# Arduino_UNO_Zeno_Version_2021-05-13.net
KiCad netlist of a schematic drawn in EasyEDA
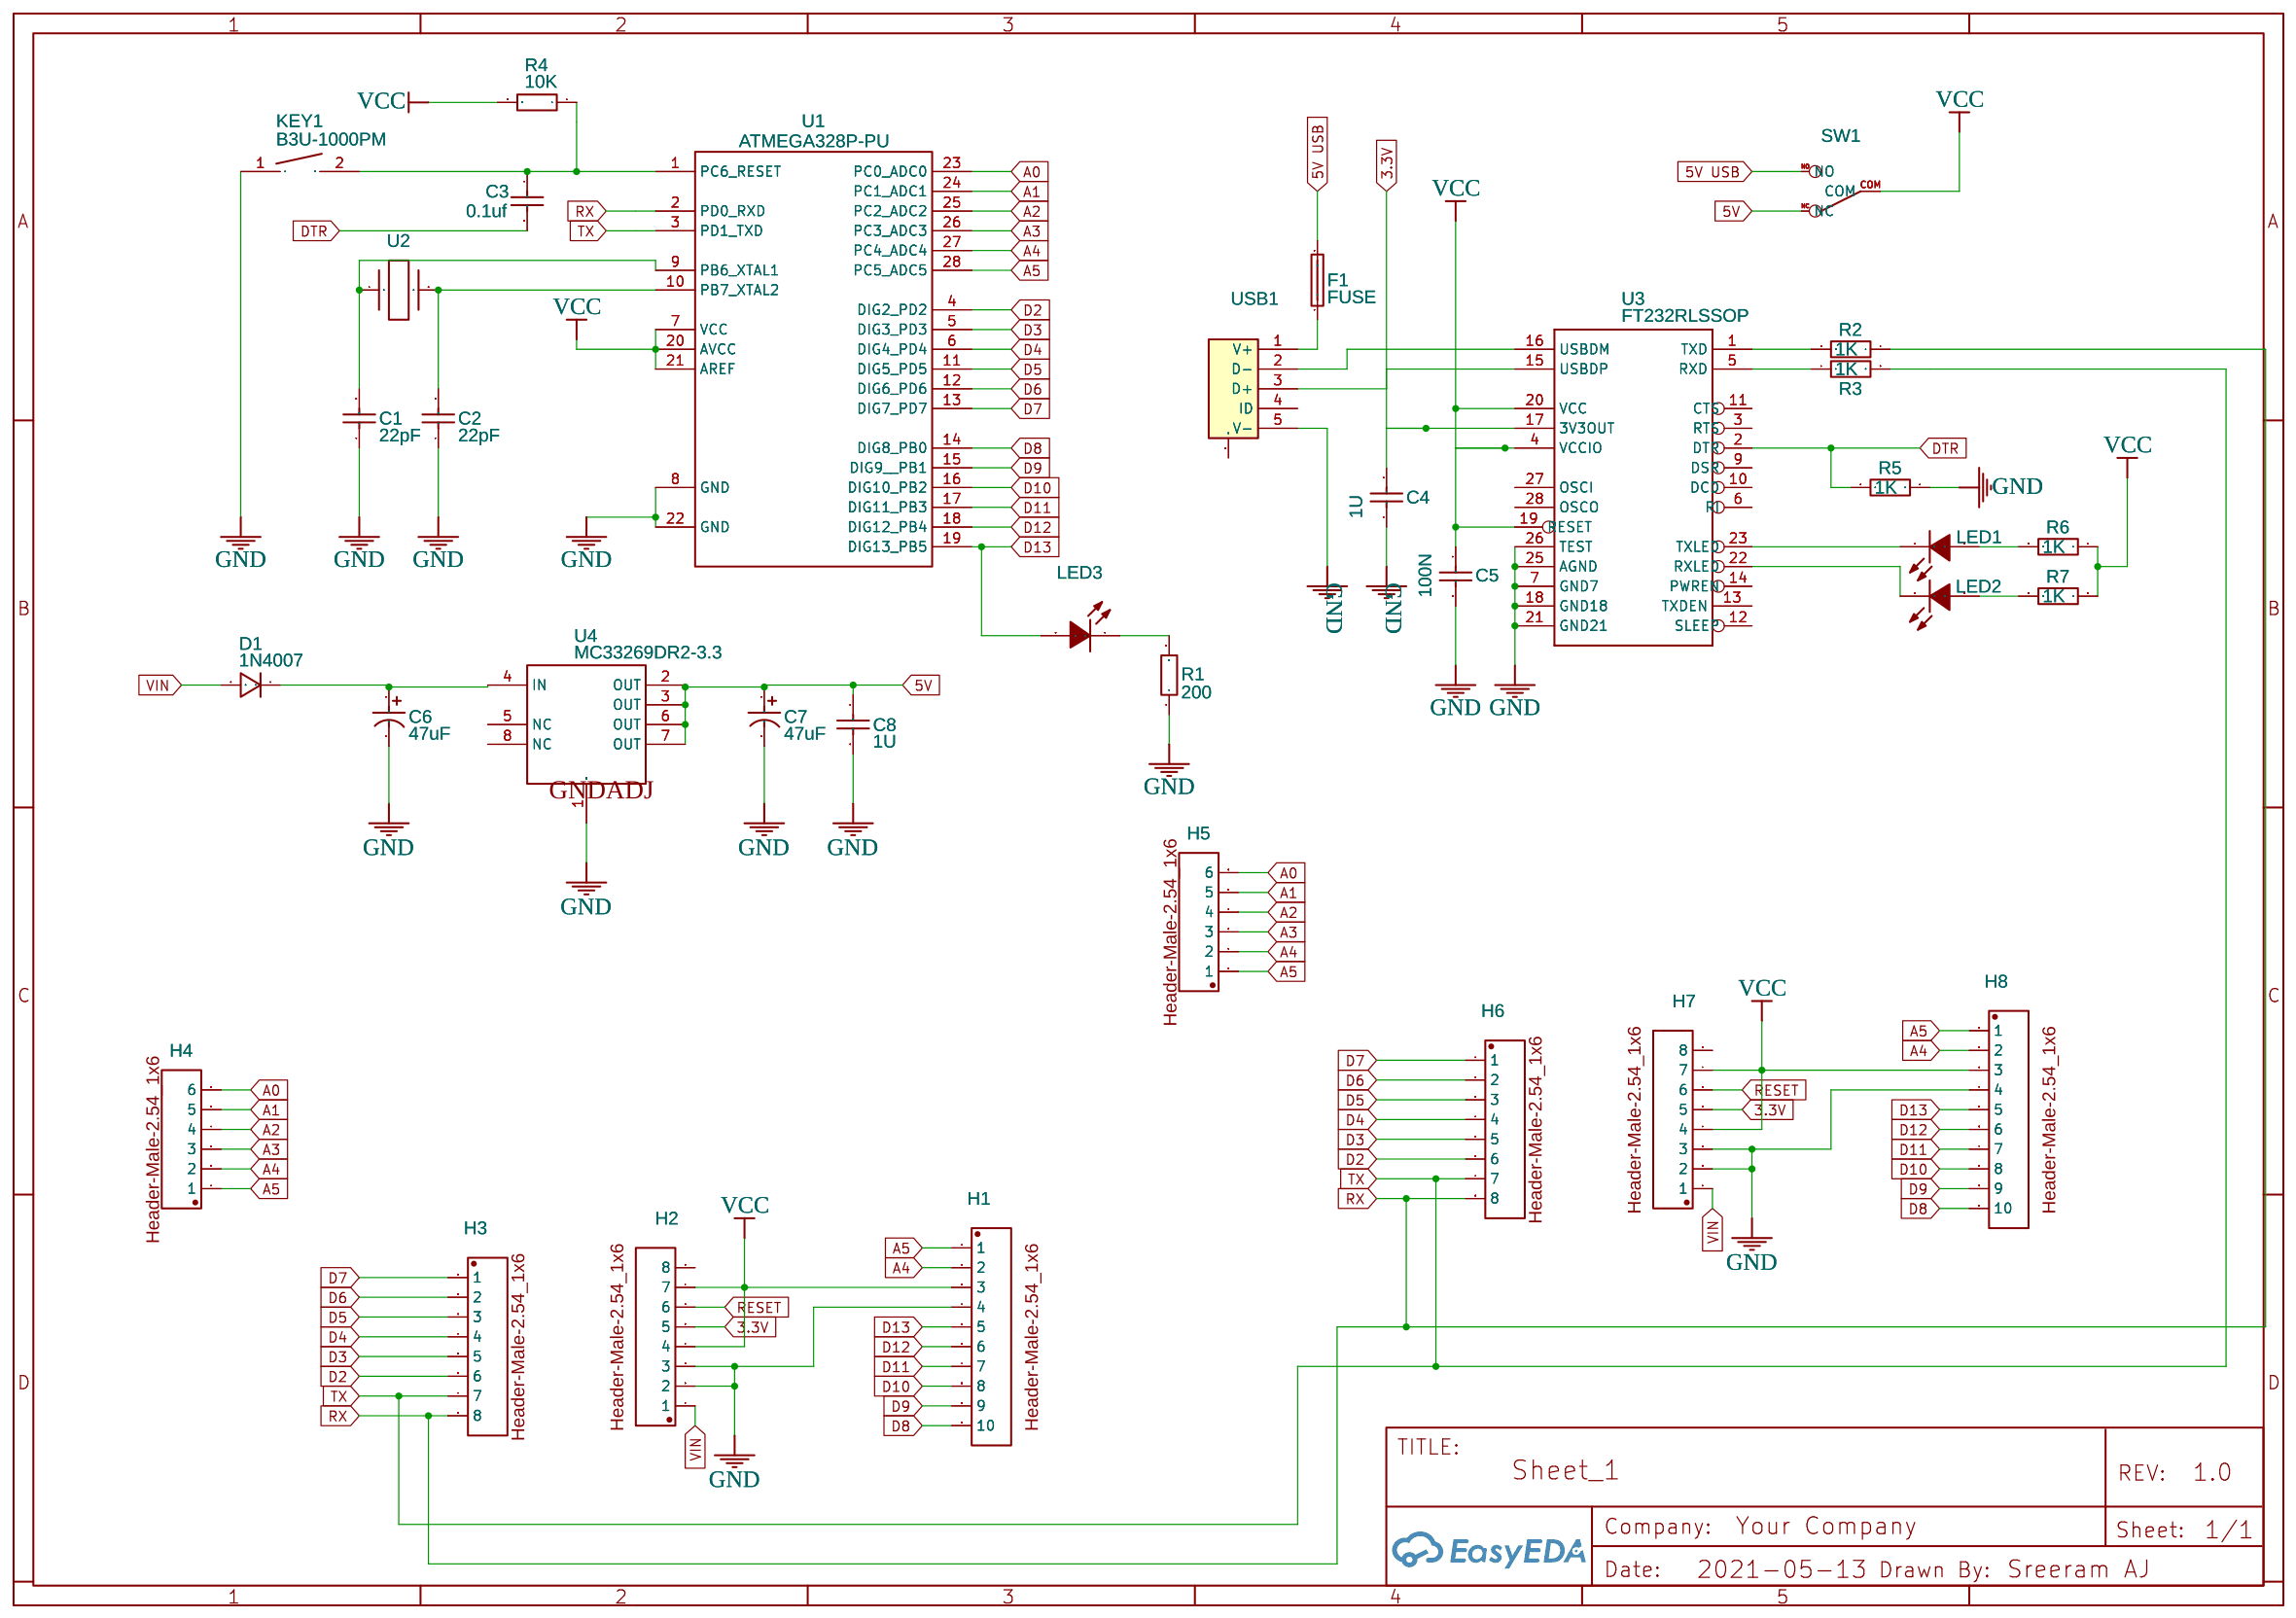
[diagram p0: schematic sheet]

(export (version "E")
  (design (tool "Eeschema 10.0.6"))
  (components
    (comp (ref "C1")
      (value "22pF")
      (fields
        (field (name "BOM_Manufacturer Part") "1206CG220J500NT")
        (field (name "BOM_Supplier Part") "C1896")
      )
      (libsource (lib "") (part "CAPACITOR SMD  22pF 1206"))
    )
    (comp (ref "C2")
      (value "22pF")
      (fields
        (field (name "BOM_Manufacturer Part") "1206CG220J500NT")
        (field (name "BOM_Supplier Part") "C1896")
      )
      (libsource (lib "") (part "CAPACITOR SMD  22pF 1206"))
    )
    (comp (ref "C3")
      (value "0.1uf")
      (fields
        (field (name "BOM_Manufacturer Part") "1206CG220J500NT")
        (field (name "BOM_Supplier Part") "C1896")
      )
      (libsource (lib "") (part "CAPACITOR SMD  22pF 1206_1"))
    )
    (comp (ref "C4")
      (value "1U")
      (fields
        (field (name "BOM_Manufacturer Part") "1206CG220J500NT")
        (field (name "BOM_Supplier Part") "C1896")
      )
      (libsource (lib "") (part "CAPACITOR SMD  22pF 1206"))
    )
    (comp (ref "C5")
      (value "100N")
      (fields
        (field (name "BOM_Manufacturer Part") "1206CG220J500NT")
        (field (name "BOM_Supplier Part") "C1896")
      )
      (libsource (lib "") (part "CAPACITOR SMD  22pF 1206_1"))
    )
    (comp (ref "C6")
      (value "47uF")
      (fields
        (field (name "BOM_Manufacturer Part") "EEE-1JA470UP")
        (field (name "BOM_Supplier Part") "PCE3946CT-ND")
      )
      (libsource (lib "") (part "PCE3946CT-ND 47UF 63V SMD CAPACITOR"))
    )
    (comp (ref "C7")
      (value "47uF")
      (fields
        (field (name "BOM_Manufacturer Part") "EEE-1JA470UP")
        (field (name "BOM_Supplier Part") "PCE3946CT-ND")
      )
      (libsource (lib "") (part "PCE3946CT-ND 47UF 63V SMD CAPACITOR"))
    )
    (comp (ref "C8")
      (value "1U")
      (fields
        (field (name "BOM_Manufacturer Part") "1206CG220J500NT")
        (field (name "BOM_Supplier Part") "C1896")
      )
      (libsource (lib "") (part "CAPACITOR SMD  22pF 1206_1"))
    )
    (comp (ref "D1")
      (value "1N4007")
      (fields (field (name "BOM_Supplier Part") "C126233"))
      (libsource (lib "") (part "DIODE 1N4007 SMD 5X2.56"))
    )
    (comp (ref "F1")
      (value "FUSE")
      (fields
        (field (name "BOM_Manufacturer Part") "1812L020PR")
        (field (name "BOM_Supplier Part") "C151167")
      )
      (libsource (lib "") (part "1812L020PR"))
    )
    (comp (ref "H1") (value "Header-Male-2.54_1x10") (libsource (lib "") (part "Header-Male-2.54_1x10")))
    (comp (ref "H2") (value "HEADER-MALE-2.54_1X8") (libsource (lib "") (part "HEADER-MALE-2.54_1X8_1")))
    (comp (ref "H3") (value "K") (libsource (lib "") (part "HEADER-MALE-2.54_1X8")))
    (comp (ref "H4") (value "Header-Male-2.54_1x6") (libsource (lib "") (part "Header-Male-2.54_1x6")))
    (comp (ref "H5") (value "Header-Male-2.54_1x6") (libsource (lib "") (part "Header-Male-2.54_1x6")))
    (comp (ref "H6") (value "K") (libsource (lib "") (part "HEADER-MALE-2.54_1X8")))
    (comp (ref "H7") (value "HEADER-MALE-2.54_1X8") (libsource (lib "") (part "HEADER-MALE-2.54_1X8_1")))
    (comp (ref "H8") (value "Header-Male-2.54_1x10") (libsource (lib "") (part "Header-Male-2.54_1x10")))
    (comp (ref "KEY1")
      (value "B3U-1000PM")
      (fields (field (name "BOM_Supplier Part") "C271754"))
      (libsource (lib "") (part "B3U-1000PM"))
    )
    (comp (ref "LED1") (value "LED SMD 0603") (libsource (lib "") (part "LED SMD 0603")))
    (comp (ref "LED2") (value "LED SMD 0603") (libsource (lib "") (part "LED SMD 0603")))
    (comp (ref "LED3") (value "LED SMD 0603") (libsource (lib "") (part "LED SMD 0603_1")))
    (comp (ref "R1")
      (value "200")
      (fields
        (field (name "BOM_Manufacturer Part") "RS-03K102JT")
        (field (name "BOM_Supplier Part") "C73797")
      )
      (libsource (lib "") (part "1k Resistor SMD 0603 (C73797)_2"))
    )
    (comp (ref "R2")
      (value "1K")
      (fields
        (field (name "BOM_Manufacturer Part") "RS-03K102JT")
        (field (name "BOM_Supplier Part") "C73797")
      )
      (libsource (lib "") (part "1k Resistor SMD 0603 (C73797)_1"))
    )
    (comp (ref "R3")
      (value "1K")
      (fields
        (field (name "BOM_Manufacturer Part") "RS-03K102JT")
        (field (name "BOM_Supplier Part") "C73797")
      )
      (libsource (lib "") (part "1k Resistor SMD 0603 (C73797)"))
    )
    (comp (ref "R4")
      (value "10K")
      (fields
        (field (name "BOM_Manufacturer Part") "RS-03K102JT")
        (field (name "BOM_Supplier Part") "C73797")
      )
      (libsource (lib "") (part "1k Resistor SMD 0603 (C73797)_1"))
    )
    (comp (ref "R5")
      (value "1K")
      (fields
        (field (name "BOM_Manufacturer Part") "RS-03K102JT")
        (field (name "BOM_Supplier Part") "C73797")
      )
      (libsource (lib "") (part "1k Resistor SMD 0603 (C73797)_1"))
    )
    (comp (ref "R6")
      (value "1K")
      (fields
        (field (name "BOM_Manufacturer Part") "RS-03K102JT")
        (field (name "BOM_Supplier Part") "C73797")
      )
      (libsource (lib "") (part "1k Resistor SMD 0603 (C73797)_1"))
    )
    (comp (ref "R7")
      (value "1K")
      (fields
        (field (name "BOM_Manufacturer Part") "RS-03K102JT")
        (field (name "BOM_Supplier Part") "C73797")
      )
      (libsource (lib "") (part "1k Resistor SMD 0603 (C73797)_1"))
    )
    (comp (ref "SW1") (value "SW_SLIDE") (libsource (lib "") (part "SW_SLIDE")))
    (comp (ref "U1")
      (value "ATMEGA328P-PU")
      (fields (field (name "BOM_Supplier Part") "C33901"))
      (libsource (lib "") (part "ATMEGA328P-PU"))
    )
    (comp (ref "U2")
      (value "Crystal resonator 12 MHz")
      (libsource (lib "") (part "Crystal resonator 12 MHz"))
    )
    (comp (ref "U3") (value "FT232RLSSOP") (libsource (lib "") (part "FT232RLSSOP")))
    (comp (ref "U4")
      (value "MC33269DR2-3.3")
      (fields (field (name "BOM_Supplier Part") "C7301"))
      (libsource (lib "") (part "MC33269DR2-3.3"))
    )
    (comp (ref "USB1")
      (value "micro USBFemale")
      (fields (field (name "BOM_Supplier Part") "C10418"))
      (libsource (lib "") (part "micro USBFemale"))
    )
  )
  (nets
    (net (code "1") (name "3.3V") (class "Default")
      (node (ref "C4") (pin "2") (pinfunction "2_2") (pintype "input"))
      (node (ref "H2") (pin "5") (pinfunction "5_5") (pintype "unspecified"))
      (node (ref "H7") (pin "5") (pinfunction "5_5") (pintype "unspecified"))
      (node (ref "U3") (pin "17") (pinfunction "3V3OUT_17") (pintype "output"))
    )
    (net (code "2") (name "5V") (class "Default")
      (node (ref "C7") (pin "1") (pinfunction "1_1") (pintype "input"))
      (node (ref "C8") (pin "1") (pinfunction "1_1") (pintype "input"))
      (node (ref "SW1") (pin "NC") (pinfunction "NC_NC") (pintype "unspecified"))
      (node (ref "U4") (pin "2") (pinfunction "OUT_2") (pintype "passive"))
      (node (ref "U4") (pin "3") (pinfunction "OUT_3") (pintype "passive"))
      (node (ref "U4") (pin "6") (pinfunction "OUT_6") (pintype "passive"))
      (node (ref "U4") (pin "7") (pinfunction "OUT_7") (pintype "passive"))
    )
    (net (code "3") (name "5V USB") (class "Default")
      (node (ref "F1") (pin "2") (pinfunction "2_2") (pintype "unspecified"))
      (node (ref "SW1") (pin "NO") (pinfunction "NO_NO") (pintype "unspecified"))
    )
    (net (code "4") (name "A0") (class "Default")
      (node (ref "H4") (pin "6") (pinfunction "6_6") (pintype "unspecified"))
      (node (ref "H5") (pin "6") (pinfunction "6_6") (pintype "unspecified"))
      (node (ref "U1") (pin "23") (pinfunction "PC0_ADC0_23") (pintype "bidirectional"))
    )
    (net (code "5") (name "A1") (class "Default")
      (node (ref "H4") (pin "5") (pinfunction "5_5") (pintype "unspecified"))
      (node (ref "H5") (pin "5") (pinfunction "5_5") (pintype "unspecified"))
      (node (ref "U1") (pin "24") (pinfunction "PC1_ADC1_24") (pintype "bidirectional"))
    )
    (net (code "6") (name "A2") (class "Default")
      (node (ref "H4") (pin "4") (pinfunction "4_4") (pintype "unspecified"))
      (node (ref "H5") (pin "4") (pinfunction "4_4") (pintype "unspecified"))
      (node (ref "U1") (pin "25") (pinfunction "PC2_ADC2_25") (pintype "bidirectional"))
    )
    (net (code "7") (name "A3") (class "Default")
      (node (ref "H4") (pin "3") (pinfunction "3_3") (pintype "unspecified"))
      (node (ref "H5") (pin "3") (pinfunction "3_3") (pintype "unspecified"))
      (node (ref "U1") (pin "26") (pinfunction "PC3_ADC3_26") (pintype "bidirectional"))
    )
    (net (code "8") (name "A4") (class "Default")
      (node (ref "H1") (pin "2") (pinfunction "2_2") (pintype "unspecified"))
      (node (ref "H4") (pin "2") (pinfunction "2_2") (pintype "unspecified"))
      (node (ref "H5") (pin "2") (pinfunction "2_2") (pintype "unspecified"))
      (node (ref "H8") (pin "2") (pinfunction "2_2") (pintype "unspecified"))
      (node (ref "U1") (pin "27") (pinfunction "PC4_ADC4_27") (pintype "bidirectional"))
    )
    (net (code "9") (name "A5") (class "Default")
      (node (ref "H1") (pin "1") (pinfunction "1_1") (pintype "unspecified"))
      (node (ref "H4") (pin "1") (pinfunction "1_1") (pintype "unspecified"))
      (node (ref "H5") (pin "1") (pinfunction "1_1") (pintype "unspecified"))
      (node (ref "H8") (pin "1") (pinfunction "1_1") (pintype "unspecified"))
      (node (ref "U1") (pin "28") (pinfunction "PC5_ADC5_28") (pintype "bidirectional"))
    )
    (net (code "10") (name "D2") (class "Default")
      (node (ref "H3") (pin "6") (pinfunction "6_6") (pintype "unspecified"))
      (node (ref "H6") (pin "6") (pinfunction "6_6") (pintype "unspecified"))
      (node (ref "U1") (pin "4") (pinfunction "DIG2_PD2_4") (pintype "bidirectional"))
    )
    (net (code "11") (name "D3") (class "Default")
      (node (ref "H3") (pin "5") (pinfunction "5_5") (pintype "unspecified"))
      (node (ref "H6") (pin "5") (pinfunction "5_5") (pintype "unspecified"))
      (node (ref "U1") (pin "5") (pinfunction "DIG3_PD3_5") (pintype "bidirectional"))
    )
    (net (code "12") (name "D4") (class "Default")
      (node (ref "H3") (pin "4") (pinfunction "4_4") (pintype "unspecified"))
      (node (ref "H6") (pin "4") (pinfunction "4_4") (pintype "unspecified"))
      (node (ref "U1") (pin "6") (pinfunction "DIG4_PD4_6") (pintype "bidirectional"))
    )
    (net (code "13") (name "D5") (class "Default")
      (node (ref "H3") (pin "3") (pinfunction "3_3") (pintype "unspecified"))
      (node (ref "H6") (pin "3") (pinfunction "3_3") (pintype "unspecified"))
      (node (ref "U1") (pin "11") (pinfunction "DIG5_PD5_11") (pintype "bidirectional"))
    )
    (net (code "14") (name "D6") (class "Default")
      (node (ref "H3") (pin "2") (pinfunction "2_2") (pintype "unspecified"))
      (node (ref "H6") (pin "2") (pinfunction "2_2") (pintype "unspecified"))
      (node (ref "U1") (pin "12") (pinfunction "DIG6_PD6_12") (pintype "bidirectional"))
    )
    (net (code "15") (name "D7") (class "Default")
      (node (ref "H3") (pin "1") (pinfunction "1_1") (pintype "unspecified"))
      (node (ref "H6") (pin "1") (pinfunction "1_1") (pintype "unspecified"))
      (node (ref "U1") (pin "13") (pinfunction "DIG7_PD7_13") (pintype "bidirectional"))
    )
    (net (code "16") (name "D8") (class "Default")
      (node (ref "H1") (pin "10") (pinfunction "10_10") (pintype "unspecified"))
      (node (ref "H8") (pin "10") (pinfunction "10_10") (pintype "unspecified"))
      (node (ref "U1") (pin "14") (pinfunction "DIG8_PB0_14") (pintype "bidirectional"))
    )
    (net (code "17") (name "D9") (class "Default")
      (node (ref "H1") (pin "9") (pinfunction "9_9") (pintype "unspecified"))
      (node (ref "H8") (pin "9") (pinfunction "9_9") (pintype "unspecified"))
      (node (ref "U1") (pin "15") (pinfunction "DIG9__PB1_15") (pintype "bidirectional"))
    )
    (net (code "18") (name "D10") (class "Default")
      (node (ref "H1") (pin "8") (pinfunction "8_8") (pintype "unspecified"))
      (node (ref "H8") (pin "8") (pinfunction "8_8") (pintype "unspecified"))
      (node (ref "U1") (pin "16") (pinfunction "DIG10_PB2_16") (pintype "bidirectional"))
    )
    (net (code "19") (name "D11") (class "Default")
      (node (ref "H1") (pin "7") (pinfunction "7_7") (pintype "unspecified"))
      (node (ref "H8") (pin "7") (pinfunction "7_7") (pintype "unspecified"))
      (node (ref "U1") (pin "17") (pinfunction "DIG11_PB3_17") (pintype "bidirectional"))
    )
    (net (code "20") (name "D12") (class "Default")
      (node (ref "H1") (pin "6") (pinfunction "6_6") (pintype "unspecified"))
      (node (ref "H8") (pin "6") (pinfunction "6_6") (pintype "unspecified"))
      (node (ref "U1") (pin "18") (pinfunction "DIG12_PB4_18") (pintype "bidirectional"))
    )
    (net (code "21") (name "D13") (class "Default")
      (node (ref "H1") (pin "5") (pinfunction "5_5") (pintype "unspecified"))
      (node (ref "H8") (pin "5") (pinfunction "5_5") (pintype "unspecified"))
      (node (ref "LED3") (pin "2") (pinfunction "A_2") (pintype "unspecified"))
      (node (ref "U1") (pin "19") (pinfunction "DIG13_PB5_19") (pintype "bidirectional"))
    )
    (net (code "22") (name "DTR") (class "Default")
      (node (ref "C3") (pin "2") (pinfunction "2_2") (pintype "input"))
      (node (ref "R5") (pin "2") (pinfunction "2_2") (pintype "input"))
      (node (ref "U3") (pin "2") (pinfunction "DTR_2") (pintype "output"))
    )
    (net (code "23") (name "GND") (class "Default")
      (node (ref "C1") (pin "1") (pinfunction "1_1") (pintype "input"))
      (node (ref "C2") (pin "1") (pinfunction "1_1") (pintype "input"))
      (node (ref "C4") (pin "1") (pinfunction "1_1") (pintype "input"))
      (node (ref "C5") (pin "2") (pinfunction "2_2") (pintype "input"))
      (node (ref "C6") (pin "2") (pinfunction "2_2") (pintype "input"))
      (node (ref "C7") (pin "2") (pinfunction "2_2") (pintype "input"))
      (node (ref "C8") (pin "2") (pinfunction "2_2") (pintype "input"))
      (node (ref "H1") (pin "4") (pinfunction "4_4") (pintype "unspecified"))
      (node (ref "H2") (pin "2") (pinfunction "2_2") (pintype "unspecified"))
      (node (ref "H2") (pin "3") (pinfunction "3_3") (pintype "unspecified"))
      (node (ref "H7") (pin "2") (pinfunction "2_2") (pintype "unspecified"))
      (node (ref "H7") (pin "3") (pinfunction "3_3") (pintype "unspecified"))
      (node (ref "H8") (pin "4") (pinfunction "4_4") (pintype "unspecified"))
      (node (ref "KEY1") (pin "1") (pinfunction "1_1") (pintype "input"))
      (node (ref "R1") (pin "1") (pinfunction "1_1") (pintype "input"))
      (node (ref "R5") (pin "1") (pinfunction "1_1") (pintype "input"))
      (node (ref "U1") (pin "22") (pinfunction "GND_22") (pintype "passive"))
      (node (ref "U1") (pin "8") (pinfunction "GND_8") (pintype "passive"))
      (node (ref "U3") (pin "18") (pinfunction "GND18_18") (pintype "passive"))
      (node (ref "U3") (pin "21") (pinfunction "GND21_21") (pintype "passive"))
      (node (ref "U3") (pin "25") (pinfunction "AGND_25") (pintype "passive"))
      (node (ref "U3") (pin "26") (pinfunction "TEST_26") (pintype "input"))
      (node (ref "U3") (pin "7") (pinfunction "GND7_7") (pintype "passive"))
      (node (ref "U4") (pin "1") (pinfunction "GNDADJ_1") (pintype "passive"))
      (node (ref "USB1") (pin "5") (pinfunction "V-_5") (pintype "unspecified"))
    )
    (net (code "24") (name "Net-(LED1-A)") (class "Default")
      (node (ref "LED1") (pin "2") (pinfunction "A_2") (pintype "unspecified"))
      (node (ref "R6") (pin "2") (pinfunction "2_2") (pintype "input"))
    )
    (net (code "25") (name "Net-(LED1-K)") (class "Default")
      (node (ref "LED1") (pin "1") (pinfunction "K_1") (pintype "unspecified"))
      (node (ref "U3") (pin "23") (pinfunction "TXLED_23") (pintype "input"))
    )
    (net (code "26") (name "Net-(LED2-A)") (class "Default")
      (node (ref "LED2") (pin "2") (pinfunction "A_2") (pintype "unspecified"))
      (node (ref "R7") (pin "2") (pinfunction "2_2") (pintype "input"))
    )
    (net (code "27") (name "Net-(LED2-K)") (class "Default")
      (node (ref "LED2") (pin "1") (pinfunction "K_1") (pintype "unspecified"))
      (node (ref "U3") (pin "22") (pinfunction "RXLED_22") (pintype "input"))
    )
    (net (code "28") (name "Net-(LED3-K)") (class "Default")
      (node (ref "LED3") (pin "1") (pinfunction "K_1") (pintype "unspecified"))
      (node (ref "R1") (pin "2") (pinfunction "2_2") (pintype "input"))
    )
    (net (code "29") (name "Net-(U1-PB6_XTAL1)") (class "Default")
      (node (ref "C1") (pin "2") (pinfunction "2_2") (pintype "input"))
      (node (ref "U1") (pin "9") (pinfunction "PB6_XTAL1_9") (pintype "bidirectional"))
      (node (ref "U2") (pin "1") (pinfunction "1_1") (pintype "unspecified"))
    )
    (net (code "30") (name "Net-(U1-PB7_XTAL2)") (class "Default")
      (node (ref "C2") (pin "2") (pinfunction "2_2") (pintype "input"))
      (node (ref "U1") (pin "10") (pinfunction "PB7_XTAL2_10") (pintype "bidirectional"))
      (node (ref "U2") (pin "2") (pinfunction "2_2") (pintype "unspecified"))
    )
    (net (code "31") (name "Net-(U1-PC6_RESET)") (class "Default")
      (node (ref "C3") (pin "1") (pinfunction "1_1") (pintype "input"))
      (node (ref "KEY1") (pin "2") (pinfunction "2_2") (pintype "input"))
      (node (ref "R4") (pin "1") (pinfunction "1_1") (pintype "input"))
      (node (ref "U1") (pin "1") (pinfunction "PC6_RESET_1") (pintype "bidirectional"))
    )
    (net (code "32") (name "Net-(U3-RXD)") (class "Default")
      (node (ref "R3") (pin "1") (pinfunction "1_1") (pintype "input"))
      (node (ref "U3") (pin "5") (pinfunction "RXD_5") (pintype "input"))
    )
    (net (code "33") (name "Net-(U3-TXD)") (class "Default")
      (node (ref "R2") (pin "2") (pinfunction "2_2") (pintype "input"))
      (node (ref "U3") (pin "1") (pinfunction "TXD_1") (pintype "output"))
    )
    (net (code "34") (name "Net-(U3-USBDM)") (class "Default")
      (node (ref "U3") (pin "16") (pinfunction "USBDM_16") (pintype "unspecified"))
      (node (ref "USB1") (pin "2") (pinfunction "D-_2") (pintype "unspecified"))
    )
    (net (code "35") (name "Net-(U3-USBDP)") (class "Default")
      (node (ref "U3") (pin "15") (pinfunction "USBDP_15") (pintype "unspecified"))
      (node (ref "USB1") (pin "3") (pinfunction "D+_3") (pintype "unspecified"))
    )
    (net (code "36") (name "Net-(U4-IN)") (class "Default")
      (node (ref "C6") (pin "1") (pinfunction "1_1") (pintype "input"))
      (node (ref "D1") (pin "1") (pinfunction "1_1") (pintype "unspecified"))
      (node (ref "U4") (pin "4") (pinfunction "IN_4") (pintype "passive"))
    )
    (net (code "37") (name "Net-(USB1-V+)") (class "Default")
      (node (ref "F1") (pin "1") (pinfunction "1_1") (pintype "unspecified"))
      (node (ref "USB1") (pin "1") (pinfunction "V+_1") (pintype "unspecified"))
    )
    (net (code "38") (name "RESET") (class "Default")
      (node (ref "H2") (pin "6") (pinfunction "6_6") (pintype "unspecified"))
      (node (ref "H7") (pin "6") (pinfunction "6_6") (pintype "unspecified"))
    )
    (net (code "39") (name "RX") (class "Default")
      (node (ref "H3") (pin "8") (pinfunction "8_8") (pintype "unspecified"))
      (node (ref "H6") (pin "8") (pinfunction "8_8") (pintype "unspecified"))
      (node (ref "R2") (pin "1") (pinfunction "1_1") (pintype "input"))
      (node (ref "U1") (pin "2") (pinfunction "PD0_RXD_2") (pintype "bidirectional"))
    )
    (net (code "40") (name "TX") (class "Default")
      (node (ref "H3") (pin "7") (pinfunction "7_7") (pintype "unspecified"))
      (node (ref "H6") (pin "7") (pinfunction "7_7") (pintype "unspecified"))
      (node (ref "R3") (pin "2") (pinfunction "2_2") (pintype "input"))
      (node (ref "U1") (pin "3") (pinfunction "PD1_TXD_3") (pintype "bidirectional"))
    )
    (net (code "41") (name "VCC") (class "Default")
      (node (ref "C5") (pin "1") (pinfunction "1_1") (pintype "input"))
      (node (ref "H1") (pin "3") (pinfunction "3_3") (pintype "unspecified"))
      (node (ref "H2") (pin "4") (pinfunction "4_4") (pintype "unspecified"))
      (node (ref "H2") (pin "7") (pinfunction "7_7") (pintype "unspecified"))
      (node (ref "H7") (pin "4") (pinfunction "4_4") (pintype "unspecified"))
      (node (ref "H7") (pin "7") (pinfunction "7_7") (pintype "unspecified"))
      (node (ref "H8") (pin "3") (pinfunction "3_3") (pintype "unspecified"))
      (node (ref "R4") (pin "2") (pinfunction "2_2") (pintype "input"))
      (node (ref "R6") (pin "1") (pinfunction "1_1") (pintype "input"))
      (node (ref "R7") (pin "1") (pinfunction "1_1") (pintype "input"))
      (node (ref "SW1") (pin "COM") (pinfunction "COM_COM") (pintype "unspecified"))
      (node (ref "U1") (pin "20") (pinfunction "AVCC_20") (pintype "passive"))
      (node (ref "U1") (pin "21") (pinfunction "AREF_21") (pintype "passive"))
      (node (ref "U1") (pin "7") (pinfunction "VCC_7") (pintype "passive"))
      (node (ref "U3") (pin "19") (pinfunction "RESET_19") (pintype "input"))
      (node (ref "U3") (pin "20") (pinfunction "VCC_20") (pintype "passive"))
      (node (ref "U3") (pin "4") (pinfunction "VCCIO_4") (pintype "passive"))
    )
    (net (code "42") (name "VIN") (class "Default")
      (node (ref "D1") (pin "2") (pinfunction "2_2") (pintype "unspecified"))
      (node (ref "H2") (pin "1") (pinfunction "1_1") (pintype "unspecified"))
      (node (ref "H7") (pin "1") (pinfunction "1_1") (pintype "unspecified"))
    )
    (net (code "43") (name "unconnected-(H2-Pad8)") (class "Default")
      (node (ref "H2") (pin "8") (pinfunction "8_8") (pintype "unspecified"))
    )
    (net (code "44") (name "unconnected-(H7-Pad8)") (class "Default")
      (node (ref "H7") (pin "8") (pinfunction "8_8") (pintype "unspecified"))
    )
    (net (code "45") (name "unconnected-(U3-CTS-Pad11)") (class "Default")
      (node (ref "U3") (pin "11") (pinfunction "CTS_11") (pintype "input"))
    )
    (net (code "46") (name "unconnected-(U3-DCD-Pad10)") (class "Default")
      (node (ref "U3") (pin "10") (pinfunction "DCD_10") (pintype "input"))
    )
    (net (code "47") (name "unconnected-(U3-DSR-Pad9)") (class "Default")
      (node (ref "U3") (pin "9") (pinfunction "DSR_9") (pintype "input"))
    )
    (net (code "48") (name "unconnected-(U3-OSCI-Pad27)") (class "Default")
      (node (ref "U3") (pin "27") (pinfunction "OSCI_27") (pintype "input"))
    )
    (net (code "49") (name "unconnected-(U3-OSCO-Pad28)") (class "Default")
      (node (ref "U3") (pin "28") (pinfunction "OSCO_28") (pintype "output"))
    )
    (net (code "50") (name "unconnected-(U3-PWREN-Pad14)") (class "Default")
      (node (ref "U3") (pin "14") (pinfunction "PWREN_14") (pintype "input"))
    )
    (net (code "51") (name "unconnected-(U3-RI-Pad6)") (class "Default")
      (node (ref "U3") (pin "6") (pinfunction "RI_6") (pintype "input"))
    )
    (net (code "52") (name "unconnected-(U3-RTS-Pad3)") (class "Default")
      (node (ref "U3") (pin "3") (pinfunction "RTS_3") (pintype "output"))
    )
    (net (code "53") (name "unconnected-(U3-SLEEP-Pad12)") (class "Default")
      (node (ref "U3") (pin "12") (pinfunction "SLEEP_12") (pintype "input"))
    )
    (net (code "54") (name "unconnected-(U3-TXDEN-Pad13)") (class "Default")
      (node (ref "U3") (pin "13") (pinfunction "TXDEN_13") (pintype "input"))
    )
    (net (code "55") (name "unconnected-(U4-NC-Pad5)") (class "Default")
      (node (ref "U4") (pin "5") (pinfunction "NC_5") (pintype "unspecified"))
    )
    (net (code "56") (name "unconnected-(U4-NC-Pad8)") (class "Default")
      (node (ref "U4") (pin "8") (pinfunction "NC_8") (pintype "unspecified"))
    )
    (net (code "57") (name "unconnected-(USB1-ID-Pad4)") (class "Default")
      (node (ref "USB1") (pin "4") (pinfunction "ID_4") (pintype "unspecified"))
    )
    (net (code "58") (name "unconnected-(USB1-MTN-Pad0)") (class "Default")
      (node (ref "USB1") (pin "0") (pinfunction "MTN_0") (pintype "input"))
    )
  )
)
